# Power.net
KiCad netlist of a schematic drawn in Altium Designer
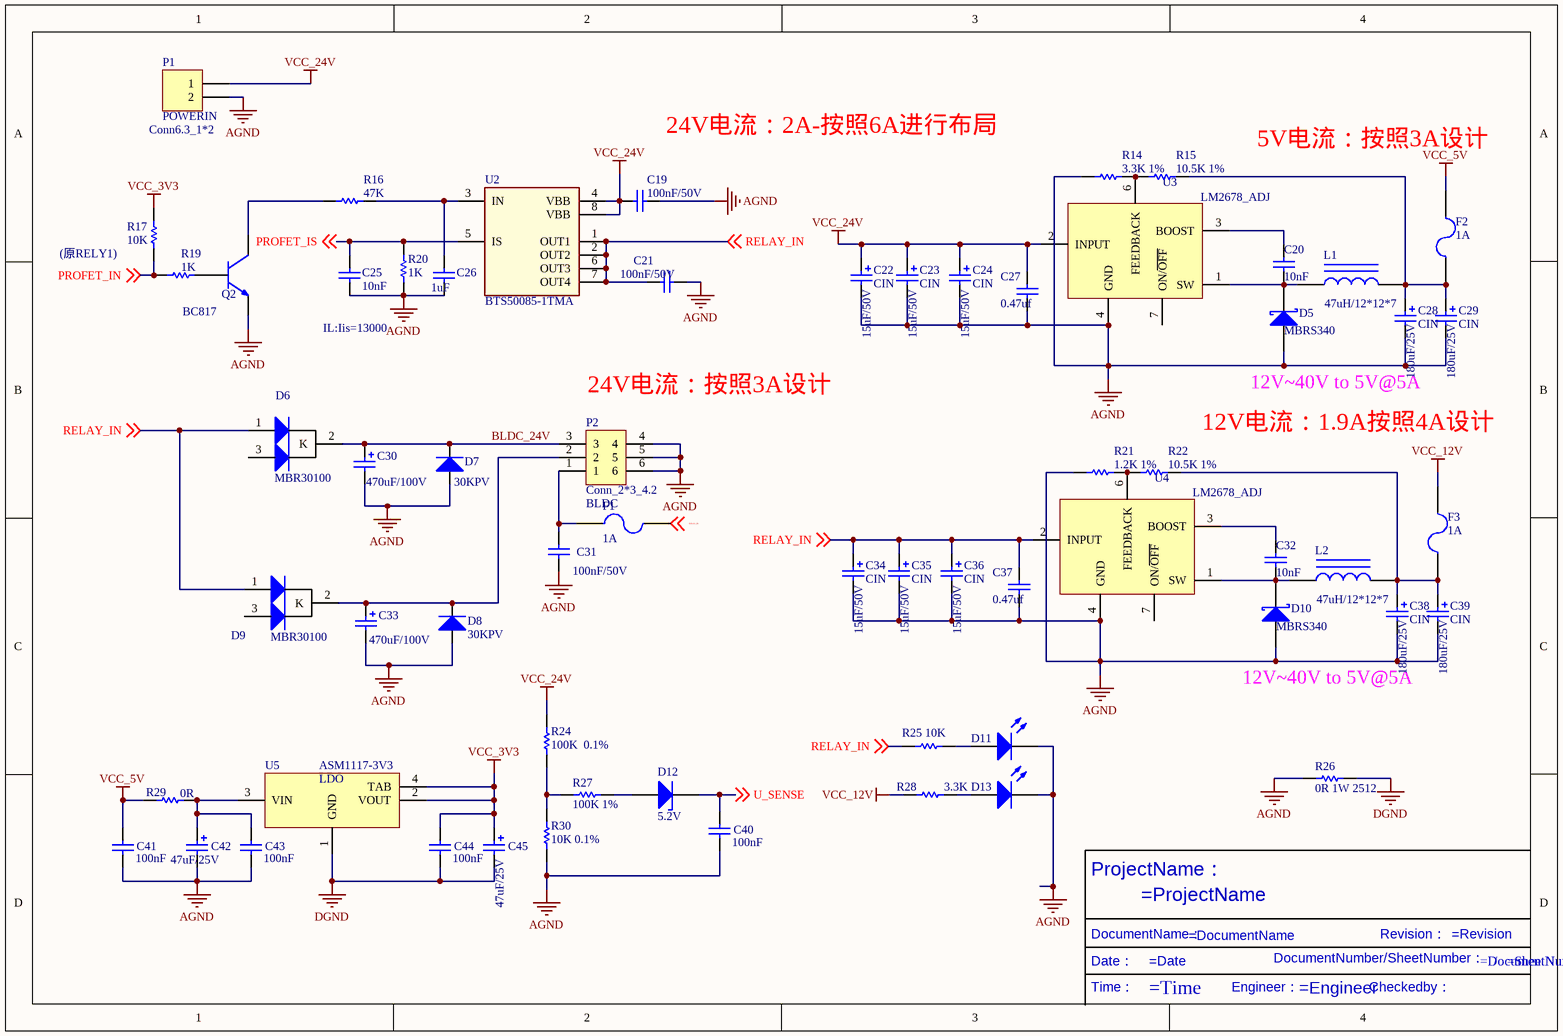
[diagram p0: Power.SchDoc]

(export (version "E")
  (design (tool "Eeschema 10.0.6"))
  (components
    (comp (ref "C19")
      (value "100nF/50V")
      (footprint "C0805")
      (description "Capacitor")
      (fields (field (name "Comment") "Cap") (field (name "PUBLISHER") "Altium Limited"))
      (libsource (lib "boocax_schlib") (part "Cap"))
    )
    (comp (ref "C20")
      (value "10nF")
      (footprint "C0805")
      (description "Capacitor")
      (fields (field (name "Comment") "Cap") (field (name "PUBLISHER") "Altium Limited"))
      (libsource (lib "boocax_schlib") (part "Cap"))
    )
    (comp (ref "C21")
      (value "100nF/50V")
      (footprint "C0805")
      (description "Capacitor")
      (fields (field (name "Comment") "Cap") (field (name "PUBLISHER") "Altium Limited"))
      (libsource (lib "boocax_schlib") (part "Cap"))
    )
    (comp (ref "C22")
      (value "CIN")
      (footprint "CAP-7343")
      (description "Polarized Capacitor (Radial)")
      (fields (field (name "ALTIUM_VALUE") "15uF/50V") (field (name "PUBLISHER") "Altium Limited"))
      (libsource (lib "boocax_schlib") (part "Cap Pol1"))
    )
    (comp (ref "C23")
      (value "CIN")
      (footprint "CAP-7343")
      (description "Polarized Capacitor (Radial)")
      (fields (field (name "ALTIUM_VALUE") "15uF/50V") (field (name "PUBLISHER") "Altium Limited"))
      (libsource (lib "boocax_schlib") (part "Cap Pol1"))
    )
    (comp (ref "C24")
      (value "CIN")
      (footprint "CAP-7343")
      (description "Polarized Capacitor (Radial)")
      (fields (field (name "ALTIUM_VALUE") "15uF/50V") (field (name "PUBLISHER") "Altium Limited"))
      (libsource (lib "boocax_schlib") (part "Cap Pol1"))
    )
    (comp (ref "C25")
      (value "10nF")
      (footprint "C0805")
      (description "Capacitor")
      (fields (field (name "Comment") "Cap") (field (name "PUBLISHER") "Altium Limited"))
      (libsource (lib "boocax_schlib") (part "Cap"))
    )
    (comp (ref "C26")
      (value "1uF")
      (footprint "C0805")
      (description "Capacitor")
      (fields (field (name "Comment") "Cap") (field (name "PUBLISHER") "Altium Limited"))
      (libsource (lib "boocax_schlib") (part "Cap"))
    )
    (comp (ref "C27")
      (value "0.47uf")
      (footprint "C0805")
      (description "CC")
      (fields (field (name "Comment") "Cap") (field (name "PUBLISHER") "Altium Limited"))
      (libsource (lib "boocax_schlib") (part "Cap"))
    )
    (comp (ref "C28")
      (value "CIN")
      (footprint "CAP-7343")
      (description "Polarized Capacitor (Radial)")
      (fields (field (name "ALTIUM_VALUE") "180uF/25V") (field (name "PUBLISHER") "Altium Limited"))
      (libsource (lib "boocax_schlib") (part "Cap Pol1"))
    )
    (comp (ref "C29")
      (value "CIN")
      (footprint "CAP-7343")
      (description "Polarized Capacitor (Radial)")
      (fields (field (name "ALTIUM_VALUE") "180uF/25V") (field (name "PUBLISHER") "Altium Limited"))
      (libsource (lib "boocax_schlib") (part "Cap Pol1"))
    )
    (comp (ref "C30")
      (value "470uF/100V")
      (footprint "CTH-R9-D7")
      (description "Polarized Capacitor (Radial)")
      (fields (field (name "Comment") "Cap Pol1") (field (name "PUBLISHER") "Altium Limited"))
      (libsource (lib "boocax_schlib") (part "Cap Pol1"))
    )
    (comp (ref "C31")
      (value "100nF/50V")
      (footprint "C0805")
      (description "Capacitor")
      (fields (field (name "Comment") "Cap") (field (name "PUBLISHER") "Altium Limited"))
      (libsource (lib "boocax_schlib") (part "Cap"))
    )
    (comp (ref "C32")
      (value "10nF")
      (footprint "C0805")
      (description "Capacitor")
      (fields (field (name "Comment") "Cap") (field (name "PUBLISHER") "Altium Limited"))
      (libsource (lib "boocax_schlib") (part "Cap"))
    )
    (comp (ref "C33")
      (value "470uF/100V")
      (footprint "CTH-R9-D7")
      (description "Polarized Capacitor (Radial)")
      (fields (field (name "Comment") "Cap Pol1") (field (name "PUBLISHER") "Altium Limited"))
      (libsource (lib "boocax_schlib") (part "Cap Pol1"))
    )
    (comp (ref "C34")
      (value "CIN")
      (footprint "CAP-7343")
      (description "Polarized Capacitor (Radial)")
      (fields (field (name "ALTIUM_VALUE") "15uF/50V") (field (name "PUBLISHER") "Altium Limited"))
      (libsource (lib "boocax_schlib") (part "Cap Pol1"))
    )
    (comp (ref "C35")
      (value "CIN")
      (footprint "CAP-7343")
      (description "Polarized Capacitor (Radial)")
      (fields (field (name "ALTIUM_VALUE") "15uF/50V") (field (name "PUBLISHER") "Altium Limited"))
      (libsource (lib "boocax_schlib") (part "Cap Pol1"))
    )
    (comp (ref "C36")
      (value "CIN")
      (footprint "CAP-7343")
      (description "Polarized Capacitor (Radial)")
      (fields (field (name "ALTIUM_VALUE") "15uF/50V") (field (name "PUBLISHER") "Altium Limited"))
      (libsource (lib "boocax_schlib") (part "Cap Pol1"))
    )
    (comp (ref "C37")
      (value "0.47uf")
      (footprint "C0805")
      (description "CC")
      (fields (field (name "Comment") "Cap") (field (name "PUBLISHER") "Altium Limited"))
      (libsource (lib "boocax_schlib") (part "Cap"))
    )
    (comp (ref "C38")
      (value "CIN")
      (footprint "CAP-7343")
      (description "Polarized Capacitor (Radial)")
      (fields (field (name "ALTIUM_VALUE") "180uF/25V") (field (name "PUBLISHER") "Altium Limited"))
      (libsource (lib "boocax_schlib") (part "Cap Pol1"))
    )
    (comp (ref "C39")
      (value "CIN")
      (footprint "CAP-7343")
      (description "Polarized Capacitor (Radial)")
      (fields (field (name "ALTIUM_VALUE") "180uF/25V") (field (name "PUBLISHER") "Altium Limited"))
      (libsource (lib "boocax_schlib") (part "Cap Pol1"))
    )
    (comp (ref "C40")
      (value "100nF")
      (footprint "C0805")
      (description "Capacitor")
      (fields (field (name "Comment") "Cap") (field (name "PUBLISHER") "Altium Limited"))
      (libsource (lib "boocax_schlib") (part "Cap"))
    )
    (comp (ref "C41")
      (value "100nF")
      (footprint "C0805")
      (description "Capacitor")
      (fields (field (name "Comment") "Cap") (field (name "PUBLISHER") "Altium Limited"))
      (libsource (lib "boocax_schlib") (part "Cap"))
    )
    (comp (ref "C42")
      (value "47uF/25V")
      (footprint "CAP-1206")
      (description "Polarized Capacitor (Radial)")
      (fields (field (name "Comment") "Cap Pol1") (field (name "PUBLISHER") "Altium Limited"))
      (libsource (lib "boocax_schlib") (part "Cap Pol1"))
    )
    (comp (ref "C43")
      (value "100nF")
      (footprint "C0805")
      (description "Capacitor")
      (fields (field (name "Comment") "Cap") (field (name "PUBLISHER") "Altium Limited"))
      (libsource (lib "boocax_schlib") (part "Cap"))
    )
    (comp (ref "C44")
      (value "100nF")
      (footprint "C0805")
      (description "Capacitor")
      (fields (field (name "Comment") "Cap") (field (name "PUBLISHER") "Altium Limited"))
      (libsource (lib "boocax_schlib") (part "Cap"))
    )
    (comp (ref "C45")
      (value "47uF/25V")
      (footprint "CAP-1206")
      (description "Polarized Capacitor (Radial)")
      (fields (field (name "Comment") "Cap Pol1") (field (name "PUBLISHER") "Altium Limited"))
      (libsource (lib "boocax_schlib") (part "Cap Pol1"))
    )
    (comp (ref "D5")
      (value "MBRS340")
      (footprint "DIODE-SMC")
      (description "Schottky Diode")
      (fields (field (name "Comment") "D Schottky"))
      (libsource (lib "Miscellaneous Devices") (part "D Schottky"))
    )
    (comp (ref "D6")
      (value "MBR30100")
      (footprint "TO-263-3")
      (description "Dual Diode")
      (fields (field (name "PUBLISHER") "Altium Limited"))
      (libsource (lib "boocax_schlib") (part "MBR30100"))
    )
    (comp (ref "D7")
      (value "TVS")
      (footprint "DIODE")
      (description "TVS保护")
      (fields (field (name "TYPE") "30KPV") (field (name "PUBLISHER") "Altium Limited"))
      (libsource (lib "fszhang") (part "TVS"))
    )
    (comp (ref "D8")
      (value "TVS")
      (footprint "DIODE")
      (description "TVS保护")
      (fields (field (name "TYPE") "30KPV") (field (name "PUBLISHER") "Altium Limited"))
      (libsource (lib "fszhang") (part "TVS"))
    )
    (comp (ref "D9")
      (value "MBR30100")
      (footprint "TO-263-3")
      (description "Dual Diode")
      (fields (field (name "PUBLISHER") "Altium Limited"))
      (libsource (lib "boocax_schlib") (part "MBR30100"))
    )
    (comp (ref "D10")
      (value "MBRS340")
      (footprint "DIODE-SMC")
      (description "Schottky Diode")
      (fields (field (name "Comment") "D Schottky"))
      (libsource (lib "Miscellaneous Devices") (part "D Schottky"))
    )
    (comp (ref "D11")
      (value "LED0")
      (footprint "LED_0805")
      (description "发光二极管")
      (fields (field (name "PUBLISHER") "Altium Limited"))
      (libsource (lib "founder") (part "LED0"))
    )
    (comp (ref "D12")
      (value "5.2V")
      (footprint "DIODE-1206")
      (description "稳压二极管")
      (fields (field (name "Comment") "Diode-Z") (field (name "PUBLISHER") "Altium Limited"))
      (libsource (lib "Sensor_V1.0.0") (part "Diode-Z"))
    )
    (comp (ref "D13")
      (value "LED0")
      (footprint "LED_0805")
      (description "发光二极管")
      (fields (field (name "PUBLISHER") "Altium Limited"))
      (libsource (lib "founder") (part "LED0"))
    )
    (comp (ref "F1")
      (value "1A")
      (footprint "1812")
      (description "保险丝")
      (fields (field (name "Comment") "Fuse") (field (name "PUBLISHER") "Altium Limited"))
      (libsource (lib "Fszhang") (part "Fuse 2"))
    )
    (comp (ref "F2")
      (value "1A")
      (footprint "1812")
      (description "保险丝")
      (fields (field (name "Comment") "Fuse") (field (name "PUBLISHER") "Altium Limited"))
      (libsource (lib "Fszhang") (part "Fuse 2"))
    )
    (comp (ref "F3")
      (value "1A")
      (footprint "1812")
      (description "保险丝")
      (fields (field (name "Comment") "Fuse") (field (name "PUBLISHER") "Altium Limited"))
      (libsource (lib "Fszhang") (part "Fuse 2"))
    )
    (comp (ref "L1")
      (value "47uH/12*12*7")
      (footprint "L-SMD-12")
      (description "Magnetic-Core Inductor")
      (fields (field (name "Comment") "Inductor Iron") (field (name "PUBLISHER") "Altium Limited"))
      (libsource (lib "boocax_schlib") (part "Inductor Iron"))
    )
    (comp (ref "L2")
      (value "47uH/12*12*7")
      (footprint "L-SMD-12")
      (description "Magnetic-Core Inductor")
      (fields (field (name "Comment") "Inductor Iron") (field (name "PUBLISHER") "Altium Limited"))
      (libsource (lib "boocax_schlib") (part "Inductor Iron"))
    )
    (comp (ref "P1")
      (value "POWERIN")
      (footprint "DIP2*6.3")
      (description "Conn6.3_1*2")
      (libsource (lib "Miscellaneous Connectors") (part "Header 2"))
    )
    (comp (ref "P2")
      (value "Conn_2*3_4.2")
      (footprint "PIN2X3_4.2")
      (fields (field (name "CONN4.2") "BLDC"))
      (libsource (lib "boocax_schlib") (part "Conn_2*3_4.2"))
    )
    (comp (ref "Q2")
      (value "BC817")
      (footprint "SOT-23_N")
      (description "NPN 45V 功耗 310mW")
      (libsource (lib "Schlib1") (part "mNPN"))
    )
    (comp (ref "R14")
      (value "3.3K 1%")
      (footprint "R0805")
      (description "Resistor")
      (fields (field (name "Comment") "Res1") (field (name "PUBLISHER") "Altium Limited"))
      (libsource (lib "boocax_schlib") (part "Res1"))
    )
    (comp (ref "R15")
      (value "10.5K 1%")
      (footprint "R0805")
      (description "Resistor")
      (fields (field (name "Comment") "Res1") (field (name "PUBLISHER") "Altium Limited"))
      (libsource (lib "boocax_schlib") (part "Res1"))
    )
    (comp (ref "R16")
      (value "47K")
      (footprint "R0805")
      (description "Resistor")
      (fields (field (name "Comment") "Res1") (field (name "PUBLISHER") "Altium Limited"))
      (libsource (lib "boocax_schlib") (part "Res1"))
    )
    (comp (ref "R17")
      (value "10K")
      (footprint "R0805")
      (description "Resistor")
      (fields (field (name "Comment") "Res1") (field (name "PUBLISHER") "Altium Limited"))
      (libsource (lib "boocax_schlib") (part "Res1"))
    )
    (comp (ref "R19")
      (value "1K")
      (footprint "R0805")
      (description "Resistor")
      (fields (field (name "Comment") "Res1") (field (name "PUBLISHER") "Altium Limited"))
      (libsource (lib "boocax_schlib") (part "Res1"))
    )
    (comp (ref "R20")
      (value "1K")
      (footprint "R0805")
      (description "Resistor")
      (fields (field (name "Comment") "Res1") (field (name "PUBLISHER") "Altium Limited"))
      (libsource (lib "boocax_schlib") (part "Res1"))
    )
    (comp (ref "R21")
      (value "1.2K 1%")
      (footprint "R0805")
      (description "Resistor")
      (fields (field (name "Comment") "Res1") (field (name "PUBLISHER") "Altium Limited"))
      (libsource (lib "boocax_schlib") (part "Res1"))
    )
    (comp (ref "R22")
      (value "10.5K 1%")
      (footprint "R0805")
      (description "Resistor")
      (fields (field (name "Comment") "Res1") (field (name "PUBLISHER") "Altium Limited"))
      (libsource (lib "boocax_schlib") (part "Res1"))
    )
    (comp (ref "R24")
      (value "100K  0.1%")
      (footprint "R0805")
      (description "Resistor")
      (fields (field (name "Comment") "Res1") (field (name "PUBLISHER") "Altium Limited"))
      (libsource (lib "boocax_schlib") (part "Res1"))
    )
    (comp (ref "R25")
      (value "10K")
      (footprint "R0805")
      (description "Resistor")
      (fields (field (name "Comment") "Res1") (field (name "PUBLISHER") "Altium Limited"))
      (libsource (lib "boocax_schlib") (part "Res1"))
    )
    (comp (ref "R26")
      (value "0R 1W 2512")
      (footprint "2512")
      (description "Resistor")
      (fields (field (name "Comment") "Res1") (field (name "PUBLISHER") "Altium Limited"))
      (libsource (lib "boocax_schlib") (part "Res1"))
    )
    (comp (ref "R27")
      (value "100K 1%")
      (footprint "R0805")
      (description "Resistor")
      (fields (field (name "Comment") "Res1") (field (name "PUBLISHER") "Altium Limited"))
      (libsource (lib "boocax_schlib") (part "Res1"))
    )
    (comp (ref "R28")
      (value "3.3K")
      (footprint "R0805")
      (description "Resistor")
      (fields (field (name "Comment") "Res1") (field (name "PUBLISHER") "Altium Limited"))
      (libsource (lib "boocax_schlib") (part "Res1"))
    )
    (comp (ref "R29")
      (value "0R")
      (footprint "R0805")
      (description "Resistor")
      (fields (field (name "Comment") "Res1") (field (name "PUBLISHER") "Altium Limited"))
      (libsource (lib "boocax_schlib") (part "Res1"))
    )
    (comp (ref "R30")
      (value "10K 0.1%")
      (footprint "R0805")
      (description "Resistor")
      (fields (field (name "Comment") "Res1") (field (name "PUBLISHER") "Altium Limited"))
      (libsource (lib "boocax_schlib") (part "Res1"))
    )
    (comp (ref "U2")
      (value "BTS50085-1TMA")
      (footprint "TO127P1385X450-8N-V")
      (description "Smart Highside High Current Power Switch, VBB 70V")
      (fields (field (name "MANUFACTURER") "Infineon Technologies"))
      (libsource (lib "boocax_schlib") (part "BTS50085-1TMA"))
    )
    (comp (ref "U3")
      (value "LM2678_ADJ")
      (footprint "TO-263-7")
      (libsource (lib "boocax_schlib") (part "LM2678"))
    )
    (comp (ref "U4")
      (value "LM2678_ADJ")
      (footprint "TO-263-7")
      (libsource (lib "boocax_schlib") (part "LM2678"))
    )
    (comp (ref "U5")
      (value "ASM1117-3V3")
      (footprint "ASM1117-3V3")
      (libsource (lib "boocax_schlib") (part "LDO"))
    )
  )
  (nets
    (net (code "9") (name "/BLDC_24V") (class "Default")
      (node (ref "C30") (pin "1") (pinfunction "1_1") (pintype "passive"))
      (node (ref "D6") (pin "2") (pinfunction "K_2") (pintype "passive"))
      (node (ref "D7") (pin "2") (pinfunction "K_2") (pintype "passive"))
      (node (ref "P2") (pin "3") (pinfunction "3_3") (pintype "passive"))
    )
    (net (code "19") (name "AGND") (class "Default")
      (node (ref "C19") (pin "1") (pinfunction "1_1") (pintype "passive"))
      (node (ref "C21") (pin "1") (pinfunction "1_1") (pintype "passive"))
      (node (ref "C22") (pin "2") (pinfunction "2_2") (pintype "passive"))
      (node (ref "C23") (pin "2") (pinfunction "2_2") (pintype "passive"))
      (node (ref "C24") (pin "2") (pinfunction "2_2") (pintype "passive"))
      (node (ref "C25") (pin "2") (pinfunction "2_2") (pintype "passive"))
      (node (ref "C26") (pin "2") (pinfunction "2_2") (pintype "passive"))
      (node (ref "C27") (pin "1") (pinfunction "1_1") (pintype "passive"))
      (node (ref "C28") (pin "2") (pinfunction "2_2") (pintype "passive"))
      (node (ref "C29") (pin "2") (pinfunction "2_2") (pintype "passive"))
      (node (ref "C30") (pin "2") (pinfunction "2_2") (pintype "passive"))
      (node (ref "C31") (pin "2") (pinfunction "2_2") (pintype "passive"))
      (node (ref "C33") (pin "2") (pinfunction "2_2") (pintype "passive"))
      (node (ref "C34") (pin "2") (pinfunction "2_2") (pintype "passive"))
      (node (ref "C35") (pin "2") (pinfunction "2_2") (pintype "passive"))
      (node (ref "C36") (pin "2") (pinfunction "2_2") (pintype "passive"))
      (node (ref "C37") (pin "1") (pinfunction "1_1") (pintype "passive"))
      (node (ref "C38") (pin "2") (pinfunction "2_2") (pintype "passive"))
      (node (ref "C39") (pin "2") (pinfunction "2_2") (pintype "passive"))
      (node (ref "C40") (pin "1") (pinfunction "1_1") (pintype "passive"))
      (node (ref "C41") (pin "1") (pinfunction "1_1") (pintype "passive"))
      (node (ref "C42") (pin "2") (pinfunction "2_2") (pintype "passive"))
      (node (ref "C43") (pin "1") (pinfunction "1_1") (pintype "passive"))
      (node (ref "D10") (pin "1") (pinfunction "A_1") (pintype "passive"))
      (node (ref "D11") (pin "2") (pinfunction "K_2") (pintype "passive"))
      (node (ref "D13") (pin "2") (pinfunction "K_2") (pintype "passive"))
      (node (ref "D5") (pin "1") (pinfunction "A_1") (pintype "passive"))
      (node (ref "D7") (pin "1") (pinfunction "A_1") (pintype "passive"))
      (node (ref "D8") (pin "1") (pinfunction "A_1") (pintype "passive"))
      (node (ref "P1") (pin "2") (pinfunction "2_2") (pintype "passive"))
      (node (ref "P2") (pin "4") (pinfunction "4_4") (pintype "passive"))
      (node (ref "P2") (pin "5") (pinfunction "5_5") (pintype "passive"))
      (node (ref "P2") (pin "6") (pinfunction "6_6") (pintype "passive"))
      (node (ref "Q2") (pin "2") (pinfunction "E_2") (pintype "passive"))
      (node (ref "R14") (pin "1") (pinfunction "1_1") (pintype "passive"))
      (node (ref "R20") (pin "1") (pinfunction "1_1") (pintype "passive"))
      (node (ref "R21") (pin "1") (pinfunction "1_1") (pintype "passive"))
      (node (ref "R26") (pin "1") (pinfunction "1_1") (pintype "passive"))
      (node (ref "R30") (pin "2") (pinfunction "2_2") (pintype "passive"))
      (node (ref "U3") (pin "4") (pinfunction "GND_4") (pintype "passive"))
      (node (ref "U4") (pin "4") (pinfunction "GND_4") (pintype "passive"))
    )
    (net (code "20") (name "DGND") (class "Default")
      (node (ref "C44") (pin "1") (pinfunction "1_1") (pintype "passive"))
      (node (ref "C45") (pin "2") (pinfunction "2_2") (pintype "passive"))
      (node (ref "R26") (pin "2") (pinfunction "2_2") (pintype "passive"))
      (node (ref "U5") (pin "1") (pinfunction "GND_1") (pintype "passive"))
    )
    (net (code "21") (name "Net-(C28-Pad1)") (class "Default")
      (node (ref "C28") (pin "1") (pinfunction "1_1") (pintype "passive"))
      (node (ref "C29") (pin "1") (pinfunction "1_1") (pintype "passive"))
      (node (ref "F2") (pin "1") (pinfunction "1_1") (pintype "passive"))
      (node (ref "L1") (pin "2") (pinfunction "2_2") (pintype "passive"))
      (node (ref "R15") (pin "2") (pinfunction "2_2") (pintype "passive"))
    )
    (net (code "22") (name "Net-(C31-Pad1)") (class "Default")
      (node (ref "C31") (pin "1") (pinfunction "1_1") (pintype "passive"))
      (node (ref "F1") (pin "1") (pinfunction "1_1") (pintype "passive"))
      (node (ref "P2") (pin "1") (pinfunction "1_1") (pintype "passive"))
    )
    (net (code "23") (name "Net-(C38-Pad1)") (class "Default")
      (node (ref "C38") (pin "1") (pinfunction "1_1") (pintype "passive"))
      (node (ref "C39") (pin "1") (pinfunction "1_1") (pintype "passive"))
      (node (ref "F3") (pin "1") (pinfunction "1_1") (pintype "passive"))
      (node (ref "L2") (pin "2") (pinfunction "2_2") (pintype "passive"))
      (node (ref "R22") (pin "2") (pinfunction "2_2") (pintype "passive"))
    )
    (net (code "24") (name "Net-(D5-K)") (class "Default")
      (node (ref "C20") (pin "1") (pinfunction "1_1") (pintype "passive"))
      (node (ref "D5") (pin "2") (pinfunction "K_2") (pintype "passive"))
      (node (ref "L1") (pin "1") (pinfunction "1_1") (pintype "passive"))
      (node (ref "U3") (pin "1") (pinfunction "SW_1") (pintype "passive"))
    )
    (net (code "25") (name "Net-(D8-K)") (class "Default")
      (node (ref "C33") (pin "1") (pinfunction "1_1") (pintype "passive"))
      (node (ref "D8") (pin "2") (pinfunction "K_2") (pintype "passive"))
      (node (ref "D9") (pin "2") (pinfunction "K_2") (pintype "passive"))
      (node (ref "P2") (pin "2") (pinfunction "2_2") (pintype "passive"))
    )
    (net (code "26") (name "Net-(D10-K)") (class "Default")
      (node (ref "C32") (pin "1") (pinfunction "1_1") (pintype "passive"))
      (node (ref "D10") (pin "2") (pinfunction "K_2") (pintype "passive"))
      (node (ref "L2") (pin "1") (pinfunction "1_1") (pintype "passive"))
      (node (ref "U4") (pin "1") (pinfunction "SW_1") (pintype "passive"))
    )
    (net (code "27") (name "Net-(D11-A)") (class "Default")
      (node (ref "D11") (pin "1") (pinfunction "A_1") (pintype "passive"))
      (node (ref "R25") (pin "1") (pinfunction "1_1") (pintype "passive"))
    )
    (net (code "28") (name "Net-(D12-A)") (class "Default")
      (node (ref "D12") (pin "1") (pinfunction "A_1") (pintype "passive"))
      (node (ref "R27") (pin "2") (pinfunction "2_2") (pintype "passive"))
    )
    (net (code "29") (name "Net-(D13-A)") (class "Default")
      (node (ref "D13") (pin "1") (pinfunction "A_1") (pintype "passive"))
      (node (ref "R28") (pin "1") (pinfunction "1_1") (pintype "passive"))
    )
    (net (code "30") (name "Net-(Q2-B)") (class "Default")
      (node (ref "Q2") (pin "1") (pinfunction "B_1") (pintype "passive"))
      (node (ref "R19") (pin "1") (pinfunction "1_1") (pintype "passive"))
    )
    (net (code "31") (name "Net-(Q2-C)") (class "Default")
      (node (ref "Q2") (pin "3") (pinfunction "C_3") (pintype "passive"))
      (node (ref "R16") (pin "1") (pinfunction "1_1") (pintype "passive"))
    )
    (net (code "32") (name "Net-(R24-Pad2)") (class "Default")
      (node (ref "R24") (pin "2") (pinfunction "2_2") (pintype "passive"))
      (node (ref "R27") (pin "1") (pinfunction "1_1") (pintype "passive"))
      (node (ref "R30") (pin "1") (pinfunction "1_1") (pintype "passive"))
    )
    (net (code "33") (name "Net-(U2-IN)") (class "Default")
      (node (ref "C26") (pin "1") (pinfunction "1_1") (pintype "passive"))
      (node (ref "R16") (pin "2") (pinfunction "2_2") (pintype "passive"))
      (node (ref "U2") (pin "3") (pinfunction "IN_3") (pintype "passive"))
    )
    (net (code "34") (name "Net-(U3-BOOST)") (class "Default")
      (node (ref "C20") (pin "2") (pinfunction "2_2") (pintype "passive"))
      (node (ref "U3") (pin "3") (pinfunction "BOOST_3") (pintype "passive"))
    )
    (net (code "35") (name "Net-(U3-FEEDBACK)") (class "Default")
      (node (ref "R14") (pin "2") (pinfunction "2_2") (pintype "passive"))
      (node (ref "R15") (pin "1") (pinfunction "1_1") (pintype "passive"))
      (node (ref "U3") (pin "6") (pinfunction "FEEDBACK_6") (pintype "passive"))
    )
    (net (code "36") (name "Net-(U4-BOOST)") (class "Default")
      (node (ref "C32") (pin "2") (pinfunction "2_2") (pintype "passive"))
      (node (ref "U4") (pin "3") (pinfunction "BOOST_3") (pintype "passive"))
    )
    (net (code "37") (name "Net-(U4-FEEDBACK)") (class "Default")
      (node (ref "R21") (pin "2") (pinfunction "2_2") (pintype "passive"))
      (node (ref "R22") (pin "1") (pinfunction "1_1") (pintype "passive"))
      (node (ref "U4") (pin "6") (pinfunction "FEEDBACK_6") (pintype "passive"))
    )
    (net (code "38") (name "Net-(U5-VIN)") (class "Default")
      (node (ref "C42") (pin "1") (pinfunction "1_1") (pintype "passive"))
      (node (ref "C43") (pin "2") (pinfunction "2_2") (pintype "passive"))
      (node (ref "R29") (pin "2") (pinfunction "2_2") (pintype "passive"))
      (node (ref "U5") (pin "3") (pinfunction "VIN_3") (pintype "passive"))
    )
    (net (code "39") (name "PROFET_IN") (class "Default")
      (node (ref "R17") (pin "2") (pinfunction "2_2") (pintype "passive"))
      (node (ref "R19") (pin "2") (pinfunction "2_2") (pintype "passive"))
    )
    (net (code "40") (name "PROFET_IS") (class "Default")
      (node (ref "C25") (pin "1") (pinfunction "1_1") (pintype "passive"))
      (node (ref "R20") (pin "2") (pinfunction "2_2") (pintype "passive"))
      (node (ref "U2") (pin "5") (pinfunction "IS_5") (pintype "passive"))
    )
    (net (code "41") (name "RELAY_IN") (class "Default")
      (node (ref "C21") (pin "2") (pinfunction "2_2") (pintype "passive"))
      (node (ref "C34") (pin "1") (pinfunction "1_1") (pintype "passive"))
      (node (ref "C35") (pin "1") (pinfunction "1_1") (pintype "passive"))
      (node (ref "C36") (pin "1") (pinfunction "1_1") (pintype "passive"))
      (node (ref "C37") (pin "2") (pinfunction "2_2") (pintype "passive"))
      (node (ref "D6") (pin "1") (pinfunction "A_1") (pintype "passive"))
      (node (ref "D9") (pin "1") (pinfunction "A_1") (pintype "passive"))
      (node (ref "F1") (pin "2") (pinfunction "2_2") (pintype "passive"))
      (node (ref "R25") (pin "2") (pinfunction "2_2") (pintype "passive"))
      (node (ref "U2") (pin "1") (pinfunction "OUT1_1") (pintype "passive"))
      (node (ref "U2") (pin "2") (pinfunction "OUT2_2") (pintype "passive"))
      (node (ref "U2") (pin "6") (pinfunction "OUT3_6") (pintype "passive"))
      (node (ref "U2") (pin "7") (pinfunction "OUT4_7") (pintype "passive"))
      (node (ref "U4") (pin "2") (pinfunction "INPUT_2") (pintype "passive"))
    )
    (net (code "42") (name "U_SENSE") (class "Default")
      (node (ref "C40") (pin "2") (pinfunction "2_2") (pintype "passive"))
      (node (ref "D12") (pin "2") (pinfunction "K_2") (pintype "passive"))
    )
    (net (code "43") (name "VCC_3V3") (class "Default")
      (node (ref "C44") (pin "2") (pinfunction "2_2") (pintype "passive"))
      (node (ref "C45") (pin "1") (pinfunction "1_1") (pintype "passive"))
      (node (ref "R17") (pin "1") (pinfunction "1_1") (pintype "passive"))
      (node (ref "U5") (pin "2") (pinfunction "VOUT_2") (pintype "passive"))
      (node (ref "U5") (pin "4") (pinfunction "TAB_4") (pintype "passive"))
    )
    (net (code "44") (name "VCC_5V") (class "Default")
      (node (ref "C41") (pin "2") (pinfunction "2_2") (pintype "passive"))
      (node (ref "F2") (pin "2") (pinfunction "2_2") (pintype "passive"))
      (node (ref "R29") (pin "1") (pinfunction "1_1") (pintype "passive"))
    )
    (net (code "45") (name "VCC_12V") (class "Default")
      (node (ref "F3") (pin "2") (pinfunction "2_2") (pintype "passive"))
      (node (ref "R28") (pin "2") (pinfunction "2_2") (pintype "passive"))
    )
    (net (code "46") (name "VCC_24V") (class "Default")
      (node (ref "C19") (pin "2") (pinfunction "2_2") (pintype "passive"))
      (node (ref "C22") (pin "1") (pinfunction "1_1") (pintype "passive"))
      (node (ref "C23") (pin "1") (pinfunction "1_1") (pintype "passive"))
      (node (ref "C24") (pin "1") (pinfunction "1_1") (pintype "passive"))
      (node (ref "C27") (pin "2") (pinfunction "2_2") (pintype "passive"))
      (node (ref "P1") (pin "1") (pinfunction "1_1") (pintype "passive"))
      (node (ref "R24") (pin "1") (pinfunction "1_1") (pintype "passive"))
      (node (ref "U2") (pin "4") (pinfunction "VBB_4") (pintype "power_in"))
      (node (ref "U2") (pin "8") (pinfunction "VBB_8") (pintype "power_in"))
      (node (ref "U3") (pin "2") (pinfunction "INPUT_2") (pintype "passive"))
    )
    (net (code "47") (name "unconnected-(D6-A-Pad3)") (class "Default")
      (node (ref "D6") (pin "3") (pinfunction "A_3") (pintype "passive"))
    )
    (net (code "48") (name "unconnected-(D9-A-Pad3)") (class "Default")
      (node (ref "D9") (pin "3") (pinfunction "A_3") (pintype "passive"))
    )
    (net (code "49") (name "unconnected-(U3-ON{slash}~{OFF}-Pad7)") (class "Default")
      (node (ref "U3") (pin "7") (pinfunction "ON/~{OFF}_7") (pintype "passive"))
    )
    (net (code "50") (name "unconnected-(U4-ON{slash}~{OFF}-Pad7)") (class "Default")
      (node (ref "U4") (pin "7") (pinfunction "ON/~{OFF}_7") (pintype "passive"))
    )
  )
)
